# FlowDiagramRev2.net
KiCad netlist of a schematic drawn in Altium Designer
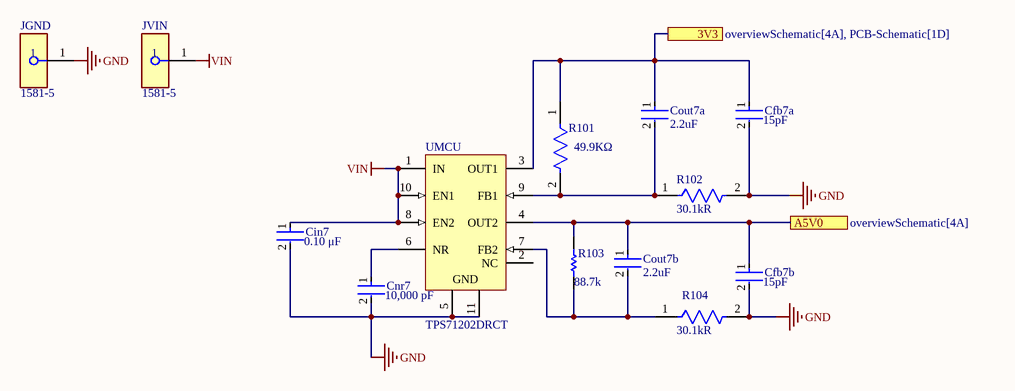
[diagram p0: FlowDiagramRev2.SchDoc]

(export (version "E")
  (design (tool "Eeschema 10.0.6"))
  (components
    (comp (ref "Cfb7a")
      (value "CC0402JRNPO9BN150")
      (footprint "FP-CC0402-0_55-IPC_B")
      (description "CAP CER 15PF 50V C0G/NPO 0402")
      (fields
        (field (name "VOLTAGE") "50V")
        (field (name "CAPACITANCE") "15pF")
        (field (name "TOLERANCE") "5%")
      )
      (libsource (lib "Altium Content Vault") (part "b4654b650e69147ec39a6b967a45e02"))
    )
    (comp (ref "Cfb7b")
      (value "CC0402JRNPO9BN150")
      (footprint "FP-CC0402-0_55-IPC_B")
      (description "CAP CER 15PF 50V C0G/NPO 0402")
      (fields
        (field (name "VOLTAGE") "50V")
        (field (name "CAPACITANCE") "15pF")
        (field (name "TOLERANCE") "5%")
      )
      (libsource (lib "Altium Content Vault") (part "b4654b650e69147ec39a6b967a45e02"))
    )
    (comp (ref "Cin7")
      (value "C0603C104M4RACTU")
      (footprint "FP-C0603C-CF-MFG")
      (description "CAP CER 0.1UF 16V X7R 0603")
      (fields
        (field (name "TOLERANCE") "0.2")
        (field (name "CAPACITANCE") "0.10 μF")
        (field (name "MANUFACTURER") "KEMET")
      )
      (libsource (lib "Altium Content Vault") (part "b4654b650e69147ec39a6b967a45e02"))
    )
    (comp (ref "Cnr7")
      (value "10,000 pF")
      (footprint "FP-C0603C-CF-MFG")
      (description "CAP CER 10000PF 50V 20% X7R 0603")
      (fields
        (field (name "MANUFACTURER PART NUMBER") "C0603C103M5RACTU")
        (field (name "MANUFACTURER") "KEMET")
      )
      (libsource (lib "Altium Content Vault") (part "b4654b650e69147ec39a6b967a45e02"))
    )
    (comp (ref "Cout7a")
      (value "GRM188R71A225KE15D")
      (footprint "FP-GRM188-0_1-e0_2_0_5-MFG")
      (description "Chip Multilayer Ceramic Capacitors for General Purpose, 0603, 2.2uF, X7R, 15%, 10%, 10V")
      (fields
        (field (name "VOLTAGE") "10V")
        (field (name "CAPACITANCE") "2.2uF")
        (field (name "TOLERANCE") "10%")
      )
      (libsource (lib "Altium Content Vault") (part "11868f565c42a9108669ba33697ecf6"))
    )
    (comp (ref "Cout7b")
      (value "GRM188R71A225KE15D")
      (footprint "FP-GRM188-0_1-e0_2_0_5-MFG")
      (description "Chip Multilayer Ceramic Capacitors for General Purpose, 0603, 2.2uF, X7R, 15%, 10%, 10V")
      (fields
        (field (name "VOLTAGE") "10V")
        (field (name "CAPACITANCE") "2.2uF")
        (field (name "TOLERANCE") "10%")
      )
      (libsource (lib "Altium Content Vault") (part "11868f565c42a9108669ba33697ecf6"))
    )
    (comp (ref "JGND")
      (value "1581-5")
      (footprint "FP-1581-5-MFG")
      (description "CONN BANANA JACK TURRET GREEN")
      (libsource (lib "Altium Content Vault") (part "c5c826e0c4b67fe3b42ef77f2d4decc"))
    )
    (comp (ref "JVIN")
      (value "1581-5")
      (footprint "FP-1581-5-MFG")
      (description "CONN BANANA JACK TURRET GREEN")
      (libsource (lib "Altium Content Vault") (part "c5c826e0c4b67fe3b42ef77f2d4decc"))
    )
    (comp (ref "R101")
      (value "RT1206FRE0749K9L")
      (footprint "FP-RT1206-MFG")
      (description "RES SMD 49.9K OHM 1% 1/4W 1206")
      (fields
        (field (name "MANUFACTURER") "Yageo")
        (field (name "RESISTANCE") "49.9KΩ")
        (field (name "TOLERANCE") "0.0002")
      )
      (libsource (lib "Altium Content Vault") (part "1029c3af85768c4190bb7ad29bc67b5"))
    )
    (comp (ref "R102")
      (value "CRCW060330K1FKEAHP")
      (footprint "FP-CRCW0603-HPe3-IPC_B")
      (description "RES Thick Film, 30.1kΩ, 1%, 0.33W, 100ppm/°C, 0603")
      (fields (field (name "TOLERANCE") "1%") (field (name "RESISTANCE") "30.1kR"))
      (libsource (lib "Altium Content Vault") (part "1029c3af85768c4190bb7ad29bc67b5"))
    )
    (comp (ref "R103")
      (value "RC0603FR-0788K7L")
      (footprint "RESC1608X55X25ML10T15")
      (fields (field (name "MANUFACTURER") "Yageo"))
      (libsource (lib "Altium Content Vault") (part "RES"))
    )
    (comp (ref "R104")
      (value "CRCW060330K1FKEAHP")
      (footprint "FP-CRCW0603-HPe3-IPC_B")
      (description "RES Thick Film, 30.1kΩ, 1%, 0.33W, 100ppm/°C, 0603")
      (fields (field (name "TOLERANCE") "1%") (field (name "RESISTANCE") "30.1kR"))
      (libsource (lib "Altium Content Vault") (part "1029c3af85768c4190bb7ad29bc67b5"))
    )
    (comp (ref "UMCU")
      (value "TPS71202DRCT")
      (footprint "DRC0010L_V")
      (fields (field (name "MANUFACTURER") "Texas Instruments"))
      (libsource (lib "Altium Content Vault") (part "TI-TPS71202DRC10-3000X1650TP"))
    )
  )
  (nets
    (net (code "1") (name "/3V3") (class "Default")
      (node (ref "Cfb7a") (pin "1") (pinfunction "1_1") (pintype "passive"))
      (node (ref "Cout7a") (pin "1") (pinfunction "1_1") (pintype "passive"))
      (node (ref "R101") (pin "1") (pinfunction "1_1") (pintype "passive"))
      (node (ref "UMCU") (pin "3") (pinfunction "OUT1_3") (pintype "power_in"))
    )
    (net (code "2") (name "/A5V0") (class "Default")
      (node (ref "Cfb7b") (pin "1") (pinfunction "1_1") (pintype "passive"))
      (node (ref "Cout7b") (pin "1") (pinfunction "1_1") (pintype "passive"))
      (node (ref "R103") (pin "2") (pinfunction "2_2") (pintype "passive"))
      (node (ref "UMCU") (pin "4") (pinfunction "OUT2_4") (pintype "power_in"))
    )
    (net (code "3") (name "GND") (class "Default")
      (node (ref "Cfb7a") (pin "2") (pinfunction "2_2") (pintype "passive"))
      (node (ref "Cfb7b") (pin "2") (pinfunction "2_2") (pintype "passive"))
      (node (ref "Cin7") (pin "2") (pinfunction "2_2") (pintype "passive"))
      (node (ref "Cnr7") (pin "2") (pinfunction "2_2") (pintype "passive"))
      (node (ref "JGND") (pin "1") (pinfunction "1_1") (pintype "passive"))
      (node (ref "R102") (pin "2") (pinfunction "2_2") (pintype "passive"))
      (node (ref "R104") (pin "2") (pinfunction "2_2") (pintype "passive"))
      (node (ref "UMCU") (pin "11") (pinfunction "GND_11") (pintype "power_in"))
      (node (ref "UMCU") (pin "5") (pinfunction "GND_5") (pintype "power_in"))
    )
    (net (code "4") (name "Net-(UMCU-FB1)") (class "Default")
      (node (ref "Cout7a") (pin "2") (pinfunction "2_2") (pintype "passive"))
      (node (ref "R101") (pin "2") (pinfunction "2_2") (pintype "passive"))
      (node (ref "R102") (pin "1") (pinfunction "1_1") (pintype "passive"))
      (node (ref "UMCU") (pin "9") (pinfunction "FB1_9") (pintype "input"))
    )
    (net (code "5") (name "Net-(UMCU-FB2)") (class "Default")
      (node (ref "Cout7b") (pin "2") (pinfunction "2_2") (pintype "passive"))
      (node (ref "R103") (pin "1") (pinfunction "1_1") (pintype "passive"))
      (node (ref "R104") (pin "1") (pinfunction "1_1") (pintype "passive"))
      (node (ref "UMCU") (pin "7") (pinfunction "FB2_7") (pintype "input"))
    )
    (net (code "6") (name "Net-(UMCU-NR)") (class "Default")
      (node (ref "Cnr7") (pin "1") (pinfunction "1_1") (pintype "passive"))
      (node (ref "UMCU") (pin "6") (pinfunction "NR_6") (pintype "passive"))
    )
    (net (code "7") (name "VIN") (class "Default")
      (node (ref "Cin7") (pin "1") (pinfunction "1_1") (pintype "passive"))
      (node (ref "JVIN") (pin "1") (pinfunction "1_1") (pintype "passive"))
      (node (ref "UMCU") (pin "1") (pinfunction "IN_1") (pintype "power_in"))
      (node (ref "UMCU") (pin "10") (pinfunction "EN1_10") (pintype "input"))
      (node (ref "UMCU") (pin "8") (pinfunction "EN2_8") (pintype "input"))
    )
    (net (code "8") (name "unconnected-(UMCU-NC-Pad2)") (class "Default")
      (node (ref "UMCU") (pin "2") (pinfunction "NC_2") (pintype "passive"))
    )
  )
)
